# keypad.net
KiCad netlist of a schematic drawn in EAGLE
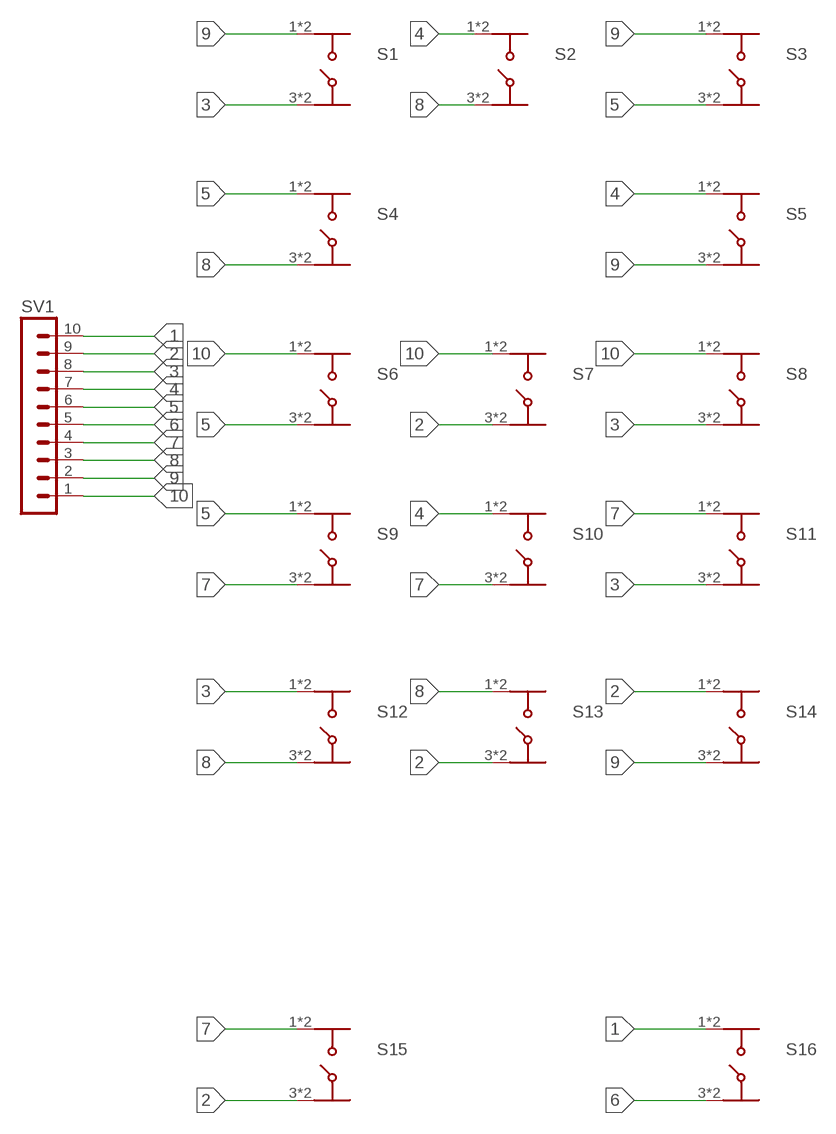
[diagram p0: schematic, sheet 1]

(export (version "E")
  (design (tool "Eeschema 10.0.6"))
  (components
    (comp (ref "S1")
      (value "430481025816")
      (footprint "eagle-import:430481025816")
      (libsource (lib "eagle-import") (part "430481025816"))
    )
    (comp (ref "S2")
      (value "430481025816")
      (footprint "eagle-import:430481025816")
      (libsource (lib "eagle-import") (part "430481025816"))
    )
    (comp (ref "S3")
      (value "430481025816")
      (footprint "eagle-import:430481025816")
      (libsource (lib "eagle-import") (part "430481025816"))
    )
    (comp (ref "S4")
      (value "430481025816")
      (footprint "eagle-import:430481025816")
      (libsource (lib "eagle-import") (part "430481025816"))
    )
    (comp (ref "S5")
      (value "430481025816")
      (footprint "eagle-import:430481025816")
      (libsource (lib "eagle-import") (part "430481025816"))
    )
    (comp (ref "S6")
      (value "430481025816")
      (footprint "eagle-import:430481025816")
      (libsource (lib "eagle-import") (part "430481025816"))
    )
    (comp (ref "S7")
      (value "430481025816")
      (footprint "eagle-import:430481025816")
      (libsource (lib "eagle-import") (part "430481025816"))
    )
    (comp (ref "S8")
      (value "430481025816")
      (footprint "eagle-import:430481025816")
      (libsource (lib "eagle-import") (part "430481025816"))
    )
    (comp (ref "S9")
      (value "430481025816")
      (footprint "eagle-import:430481025816")
      (libsource (lib "eagle-import") (part "430481025816"))
    )
    (comp (ref "S10")
      (value "430481025816")
      (footprint "eagle-import:430481025816")
      (libsource (lib "eagle-import") (part "430481025816"))
    )
    (comp (ref "S11")
      (value "430481025816")
      (footprint "eagle-import:430481025816")
      (libsource (lib "eagle-import") (part "430481025816"))
    )
    (comp (ref "S12")
      (value "430481025816")
      (footprint "eagle-import:430481025816")
      (libsource (lib "eagle-import") (part "430481025816"))
    )
    (comp (ref "S13")
      (value "430481025816")
      (footprint "eagle-import:430481025816")
      (libsource (lib "eagle-import") (part "430481025816"))
    )
    (comp (ref "S14")
      (value "430481025816")
      (footprint "eagle-import:430481025816")
      (libsource (lib "eagle-import") (part "430481025816"))
    )
    (comp (ref "S15")
      (value "430481025816")
      (footprint "eagle-import:430481025816")
      (libsource (lib "eagle-import") (part "430481025816"))
    )
    (comp (ref "S16")
      (value "430481025816")
      (footprint "eagle-import:430481025816")
      (libsource (lib "eagle-import") (part "430481025816"))
    )
    (comp (ref "SV1")
      (value "MA10-1")
      (footprint "eagle-import:MA10-1")
      (libsource (lib "eagle-import") (part "MA10-1"))
    )
  )
  (nets
    (net (code "1") (name "1") (class "Default")
      (node (ref "S16") (pin "1") (pinfunction "A_1") (pintype "power_in"))
      (node (ref "S16") (pin "2") (pinfunction "A_2") (pintype "power_in"))
      (node (ref "SV1") (pin "10") (pinfunction "10_10") (pintype "passive"))
    )
    (net (code "2") (name "2") (class "Default")
      (node (ref "S13") (pin "3") (pinfunction "B_3") (pintype "power_in"))
      (node (ref "S13") (pin "4") (pinfunction "B_4") (pintype "power_in"))
      (node (ref "S14") (pin "1") (pinfunction "A_1") (pintype "power_in"))
      (node (ref "S14") (pin "2") (pinfunction "A_2") (pintype "power_in"))
      (node (ref "S15") (pin "3") (pinfunction "B_3") (pintype "power_in"))
      (node (ref "S15") (pin "4") (pinfunction "B_4") (pintype "power_in"))
      (node (ref "S7") (pin "3") (pinfunction "B_3") (pintype "power_in"))
      (node (ref "S7") (pin "4") (pinfunction "B_4") (pintype "power_in"))
      (node (ref "SV1") (pin "9") (pinfunction "9_9") (pintype "passive"))
    )
    (net (code "3") (name "3") (class "Default")
      (node (ref "S1") (pin "3") (pinfunction "B_3") (pintype "power_in"))
      (node (ref "S1") (pin "4") (pinfunction "B_4") (pintype "power_in"))
      (node (ref "S11") (pin "3") (pinfunction "B_3") (pintype "power_in"))
      (node (ref "S11") (pin "4") (pinfunction "B_4") (pintype "power_in"))
      (node (ref "S12") (pin "1") (pinfunction "A_1") (pintype "power_in"))
      (node (ref "S12") (pin "2") (pinfunction "A_2") (pintype "power_in"))
      (node (ref "S8") (pin "3") (pinfunction "B_3") (pintype "power_in"))
      (node (ref "S8") (pin "4") (pinfunction "B_4") (pintype "power_in"))
      (node (ref "SV1") (pin "8") (pinfunction "8_8") (pintype "passive"))
    )
    (net (code "4") (name "4") (class "Default")
      (node (ref "S10") (pin "1") (pinfunction "A_1") (pintype "power_in"))
      (node (ref "S10") (pin "2") (pinfunction "A_2") (pintype "power_in"))
      (node (ref "S2") (pin "1") (pinfunction "A_1") (pintype "power_in"))
      (node (ref "S2") (pin "2") (pinfunction "A_2") (pintype "power_in"))
      (node (ref "S5") (pin "1") (pinfunction "A_1") (pintype "power_in"))
      (node (ref "S5") (pin "2") (pinfunction "A_2") (pintype "power_in"))
      (node (ref "SV1") (pin "7") (pinfunction "7_7") (pintype "passive"))
    )
    (net (code "5") (name "5") (class "Default")
      (node (ref "S3") (pin "3") (pinfunction "B_3") (pintype "power_in"))
      (node (ref "S3") (pin "4") (pinfunction "B_4") (pintype "power_in"))
      (node (ref "S4") (pin "1") (pinfunction "A_1") (pintype "power_in"))
      (node (ref "S4") (pin "2") (pinfunction "A_2") (pintype "power_in"))
      (node (ref "S6") (pin "3") (pinfunction "B_3") (pintype "power_in"))
      (node (ref "S6") (pin "4") (pinfunction "B_4") (pintype "power_in"))
      (node (ref "S9") (pin "1") (pinfunction "A_1") (pintype "power_in"))
      (node (ref "S9") (pin "2") (pinfunction "A_2") (pintype "power_in"))
      (node (ref "SV1") (pin "6") (pinfunction "6_6") (pintype "passive"))
    )
    (net (code "6") (name "6") (class "Default")
      (node (ref "S16") (pin "3") (pinfunction "B_3") (pintype "power_in"))
      (node (ref "S16") (pin "4") (pinfunction "B_4") (pintype "power_in"))
      (node (ref "SV1") (pin "5") (pinfunction "5_5") (pintype "passive"))
    )
    (net (code "7") (name "7") (class "Default")
      (node (ref "S10") (pin "3") (pinfunction "B_3") (pintype "power_in"))
      (node (ref "S10") (pin "4") (pinfunction "B_4") (pintype "power_in"))
      (node (ref "S11") (pin "1") (pinfunction "A_1") (pintype "power_in"))
      (node (ref "S11") (pin "2") (pinfunction "A_2") (pintype "power_in"))
      (node (ref "S15") (pin "1") (pinfunction "A_1") (pintype "power_in"))
      (node (ref "S15") (pin "2") (pinfunction "A_2") (pintype "power_in"))
      (node (ref "S9") (pin "3") (pinfunction "B_3") (pintype "power_in"))
      (node (ref "S9") (pin "4") (pinfunction "B_4") (pintype "power_in"))
      (node (ref "SV1") (pin "4") (pinfunction "4_4") (pintype "passive"))
    )
    (net (code "8") (name "8") (class "Default")
      (node (ref "S12") (pin "3") (pinfunction "B_3") (pintype "power_in"))
      (node (ref "S12") (pin "4") (pinfunction "B_4") (pintype "power_in"))
      (node (ref "S13") (pin "1") (pinfunction "A_1") (pintype "power_in"))
      (node (ref "S13") (pin "2") (pinfunction "A_2") (pintype "power_in"))
      (node (ref "S2") (pin "3") (pinfunction "B_3") (pintype "power_in"))
      (node (ref "S2") (pin "4") (pinfunction "B_4") (pintype "power_in"))
      (node (ref "S4") (pin "3") (pinfunction "B_3") (pintype "power_in"))
      (node (ref "S4") (pin "4") (pinfunction "B_4") (pintype "power_in"))
      (node (ref "SV1") (pin "3") (pinfunction "3_3") (pintype "passive"))
    )
    (net (code "9") (name "9") (class "Default")
      (node (ref "S1") (pin "1") (pinfunction "A_1") (pintype "power_in"))
      (node (ref "S1") (pin "2") (pinfunction "A_2") (pintype "power_in"))
      (node (ref "S14") (pin "3") (pinfunction "B_3") (pintype "power_in"))
      (node (ref "S14") (pin "4") (pinfunction "B_4") (pintype "power_in"))
      (node (ref "S3") (pin "1") (pinfunction "A_1") (pintype "power_in"))
      (node (ref "S3") (pin "2") (pinfunction "A_2") (pintype "power_in"))
      (node (ref "S5") (pin "3") (pinfunction "B_3") (pintype "power_in"))
      (node (ref "S5") (pin "4") (pinfunction "B_4") (pintype "power_in"))
      (node (ref "SV1") (pin "2") (pinfunction "2_2") (pintype "passive"))
    )
    (net (code "10") (name "10") (class "Default")
      (node (ref "S6") (pin "1") (pinfunction "A_1") (pintype "power_in"))
      (node (ref "S6") (pin "2") (pinfunction "A_2") (pintype "power_in"))
      (node (ref "S7") (pin "1") (pinfunction "A_1") (pintype "power_in"))
      (node (ref "S7") (pin "2") (pinfunction "A_2") (pintype "power_in"))
      (node (ref "S8") (pin "1") (pinfunction "A_1") (pintype "power_in"))
      (node (ref "S8") (pin "2") (pinfunction "A_2") (pintype "power_in"))
      (node (ref "SV1") (pin "1") (pinfunction "1_1") (pintype "passive"))
    )
  )
)
